# jtag.net
KiCad netlist of a schematic drawn in Altium Designer
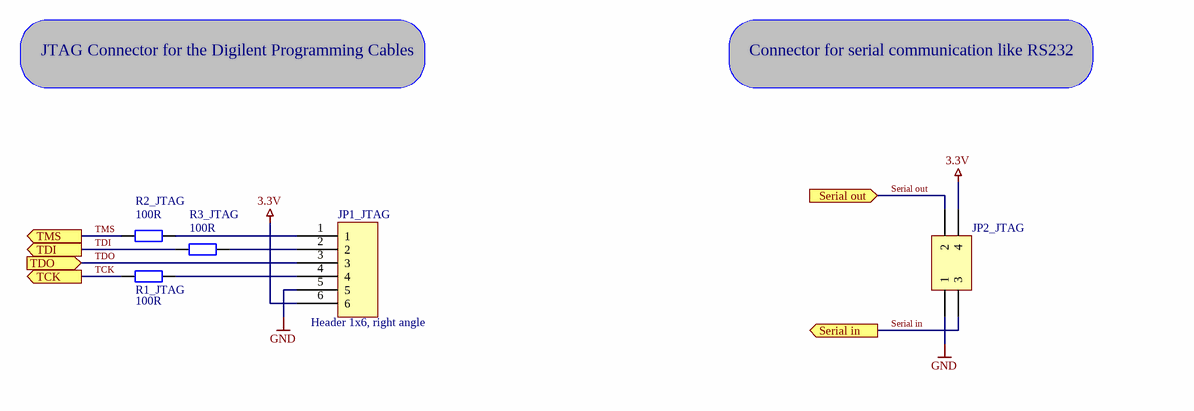
[diagram p0: jtag.SchDoc]

(export (version "E")
  (design (tool "Eeschema 10.0.6"))
  (components
    (comp (ref "JP1_JTAG")
      (value "Header 1x6, right angle")
      (footprint "HDR1X6H-90°")
      (description "Header, 6-Pin,  Right Angle")
      (fields (field (name "MANUFACTURER") "Fischer") (field (name "PART NUMBER") "SL1/53/36 Z"))
      (libsource (lib "*") (part "JTAG_CONNECTOR"))
    )
    (comp (ref "JP2_JTAG")
      (value "M22-2040205")
      (footprint "M22-2040205")
      (fields (field (name "MANUFACTURER") "HARWIN"))
      (libsource (lib "gecko3-user") (part "M22-2040205"))
    )
    (comp (ref "R1_JTAG")
      (value "100R")
      (footprint "0402")
      (description "Resistor")
      (fields
        (field (name "MANUFACTURER") "PHYCOMP")
        (field (name "PART NUMBER") "232270671001")
        (field (name "PUBLISHER") "Altium Limited")
      )
      (libsource (lib "Miscellaneous Devices") (part "Res2"))
    )
    (comp (ref "R2_JTAG")
      (value "100R")
      (footprint "0402")
      (description "Resistor")
      (fields
        (field (name "MANUFACTURER") "PHYCOMP")
        (field (name "PART NUMBER") "232270671001")
        (field (name "PUBLISHER") "Altium Limited")
      )
      (libsource (lib "Miscellaneous Devices") (part "Res2"))
    )
    (comp (ref "R3_JTAG")
      (value "100R")
      (footprint "0402")
      (description "Resistor")
      (fields
        (field (name "MANUFACTURER") "PHYCOMP")
        (field (name "PART NUMBER") "232270671001")
        (field (name "PUBLISHER") "Altium Limited")
      )
      (libsource (lib "Miscellaneous Devices") (part "Res2"))
    )
  )
  (nets
    (net (code "1") (name "/Serial in") (class "Default")
      (node (ref "JP2_JTAG") (pin "3") (pinfunction "3_3") (pintype "passive"))
    )
    (net (code "2") (name "/Serial out") (class "Default")
      (node (ref "JP2_JTAG") (pin "2") (pinfunction "2_2") (pintype "passive"))
    )
    (net (code "3") (name "/TCK") (class "Default")
      (node (ref "R1_JTAG") (pin "1") (pinfunction "1_1") (pintype "passive"))
    )
    (net (code "4") (name "/TDI") (class "Default")
      (node (ref "R3_JTAG") (pin "1") (pinfunction "1_1") (pintype "passive"))
    )
    (net (code "5") (name "/TDO") (class "Default")
      (node (ref "JP1_JTAG") (pin "3") (pinfunction "3_3") (pintype "passive"))
    )
    (net (code "6") (name "/TMS") (class "Default")
      (node (ref "R2_JTAG") (pin "1") (pinfunction "1_1") (pintype "passive"))
    )
    (net (code "7") (name "3.3V") (class "Default")
      (node (ref "JP1_JTAG") (pin "6") (pinfunction "6_6") (pintype "passive"))
      (node (ref "JP2_JTAG") (pin "4") (pinfunction "4_4") (pintype "passive"))
    )
    (net (code "8") (name "GND") (class "Default")
      (node (ref "JP1_JTAG") (pin "5") (pinfunction "5_5") (pintype "passive"))
      (node (ref "JP2_JTAG") (pin "1") (pinfunction "1_1") (pintype "passive"))
    )
    (net (code "9") (name "Net-(JP1_JTAG-Pad1)") (class "Default")
      (node (ref "JP1_JTAG") (pin "1") (pinfunction "1_1") (pintype "passive"))
      (node (ref "R2_JTAG") (pin "2") (pinfunction "2_2") (pintype "passive"))
    )
    (net (code "10") (name "Net-(JP1_JTAG-Pad2)") (class "Default")
      (node (ref "JP1_JTAG") (pin "2") (pinfunction "2_2") (pintype "passive"))
      (node (ref "R3_JTAG") (pin "2") (pinfunction "2_2") (pintype "passive"))
    )
    (net (code "11") (name "Net-(JP1_JTAG-Pad4)") (class "Default")
      (node (ref "JP1_JTAG") (pin "4") (pinfunction "4_4") (pintype "passive"))
      (node (ref "R1_JTAG") (pin "2") (pinfunction "2_2") (pintype "passive"))
    )
  )
)
